# WireBender_Remix.net
KiCad netlist of a schematic drawn in EAGLE
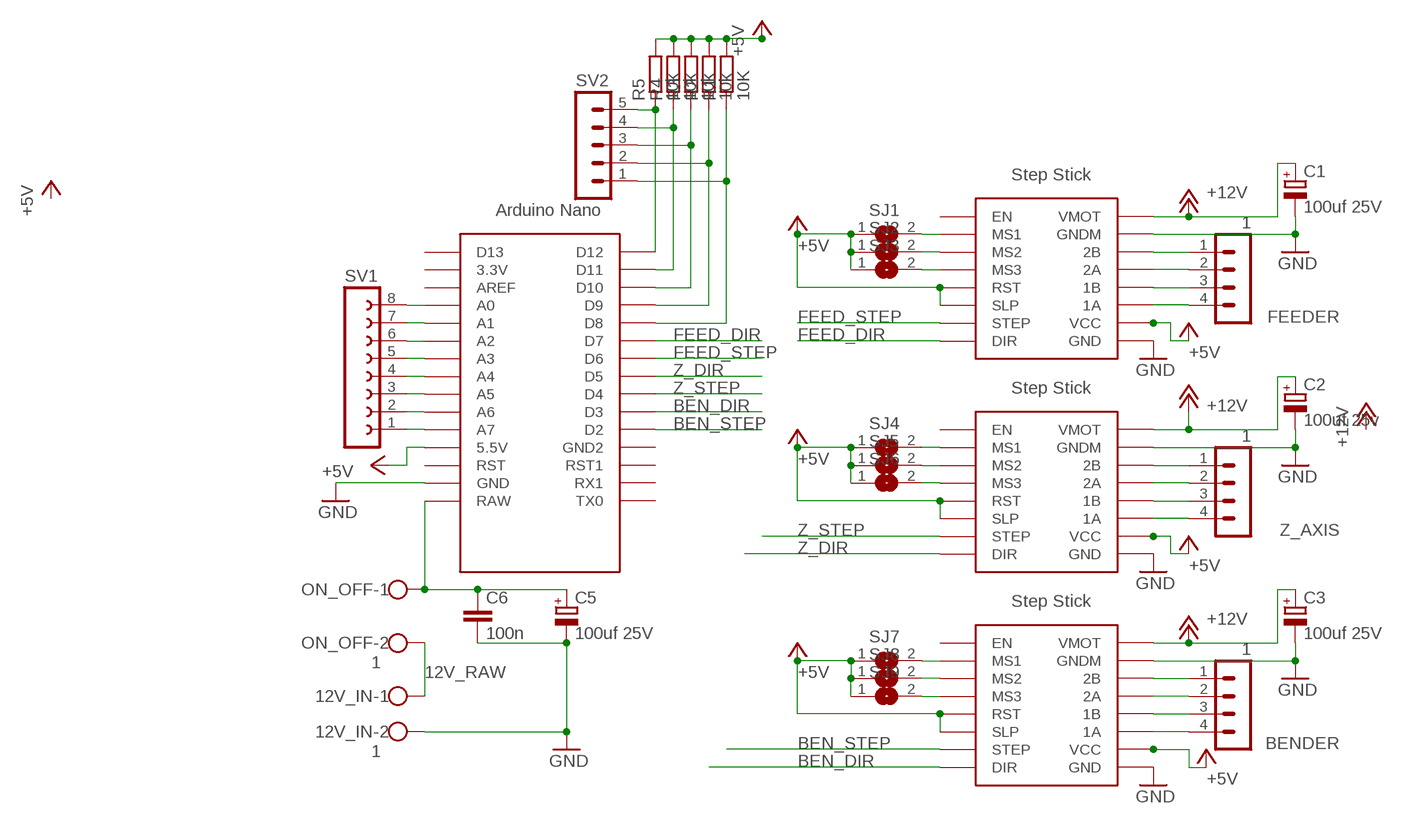
[diagram p0: schematic, sheet 1]

(export (version "E")
  (design (tool "Eeschema 10.0.6"))
  (components
    (comp (ref "12V_IN")
      (value "1")
      (footprint "eagle-import:W237-102")
      (fields (field (name "MPN") "237-102"))
      (libsource (lib "eagle-import") (part "W237-102"))
    )
    (comp (ref "BENDER")
      (value "1")
      (footprint "eagle-import:MA04-1")
      (libsource (lib "eagle-import") (part "MA04-1"))
    )
    (comp (ref "C1")
      (value "100uf 25V")
      (footprint "eagle-import:E3,5-8")
      (libsource (lib "eagle-import") (part "CPOL-EUE3.5-8"))
    )
    (comp (ref "C2")
      (value "100uf 25v")
      (footprint "eagle-import:E3,5-8")
      (libsource (lib "eagle-import") (part "CPOL-EUE3.5-8"))
    )
    (comp (ref "C3")
      (value "100uf 25V")
      (footprint "eagle-import:E3,5-8")
      (libsource (lib "eagle-import") (part "CPOL-EUE3.5-8"))
    )
    (comp (ref "C5")
      (value "100uf 25V")
      (footprint "eagle-import:E3,5-8")
      (libsource (lib "eagle-import") (part "CPOL-EUE3.5-8"))
    )
    (comp (ref "C6")
      (value "100n")
      (footprint "eagle-import:C025-030X050")
      (libsource (lib "eagle-import") (part "C-EU025-030X050"))
    )
    (comp (ref "FEEDER")
      (value "1")
      (footprint "eagle-import:MA04-1")
      (libsource (lib "eagle-import") (part "MA04-1"))
    )
    (comp (ref "FEED_DRV")
      (value "STEP-STICK")
      (footprint "eagle-import:STEP-STICK")
      (libsource (lib "eagle-import") (part "STEP-STICK"))
    )
    (comp (ref "ON_OFF")
      (value "1")
      (footprint "eagle-import:W237-102")
      (fields (field (name "MPN") "237-102"))
      (libsource (lib "eagle-import") (part "W237-102"))
    )
    (comp (ref "R1")
      (value "10K")
      (footprint "eagle-import:0207_7")
      (libsource (lib "eagle-import") (part "R-EU_0207/7"))
    )
    (comp (ref "R2")
      (value "10k")
      (footprint "eagle-import:0207_7")
      (libsource (lib "eagle-import") (part "R-EU_0207/7"))
    )
    (comp (ref "R3")
      (value "10k")
      (footprint "eagle-import:0207_7")
      (libsource (lib "eagle-import") (part "R-EU_0207/7"))
    )
    (comp (ref "R4")
      (value "10k")
      (footprint "eagle-import:0207_7")
      (libsource (lib "eagle-import") (part "R-EU_0207/7"))
    )
    (comp (ref "R5")
      (value "10k")
      (footprint "eagle-import:0207_7")
      (libsource (lib "eagle-import") (part "R-EU_0207/7"))
    )
    (comp (ref "SJ1")
      (value "SJW")
      (footprint "eagle-import:SJW")
      (libsource (lib "eagle-import") (part "SJW"))
    )
    (comp (ref "SJ2")
      (value "SJW")
      (footprint "eagle-import:SJW")
      (libsource (lib "eagle-import") (part "SJW"))
    )
    (comp (ref "SJ3")
      (value "SJW")
      (footprint "eagle-import:SJW")
      (libsource (lib "eagle-import") (part "SJW"))
    )
    (comp (ref "SJ4")
      (value "SJW")
      (footprint "eagle-import:SJW")
      (libsource (lib "eagle-import") (part "SJW"))
    )
    (comp (ref "SJ5")
      (value "SJW")
      (footprint "eagle-import:SJW")
      (libsource (lib "eagle-import") (part "SJW"))
    )
    (comp (ref "SJ6")
      (value "SJW")
      (footprint "eagle-import:SJW")
      (libsource (lib "eagle-import") (part "SJW"))
    )
    (comp (ref "SJ7")
      (value "SJW")
      (footprint "eagle-import:SJW")
      (libsource (lib "eagle-import") (part "SJW"))
    )
    (comp (ref "SJ8")
      (value "SJW")
      (footprint "eagle-import:SJW")
      (libsource (lib "eagle-import") (part "SJW"))
    )
    (comp (ref "SJ9")
      (value "SJW")
      (footprint "eagle-import:SJW")
      (libsource (lib "eagle-import") (part "SJW"))
    )
    (comp (ref "SV1")
      (value "FE08-1")
      (footprint "eagle-import:FE08")
      (libsource (lib "eagle-import") (part "FE08-1"))
    )
    (comp (ref "SV2")
      (value "MA05-1")
      (footprint "eagle-import:MA05-1")
      (libsource (lib "eagle-import") (part "MA05-1"))
    )
    (comp (ref "U$1")
      (value "NANO")
      (footprint "eagle-import:NANO")
      (libsource (lib "eagle-import") (part "NANO"))
    )
    (comp (ref "U$3")
      (value "STEP-STICK")
      (footprint "eagle-import:STEP-STICK")
      (libsource (lib "eagle-import") (part "STEP-STICK"))
    )
    (comp (ref "U$4")
      (value "STEP-STICK")
      (footprint "eagle-import:STEP-STICK")
      (libsource (lib "eagle-import") (part "STEP-STICK"))
    )
    (comp (ref "Z_AXIS")
      (value "1")
      (footprint "eagle-import:MA04-1")
      (libsource (lib "eagle-import") (part "MA04-1"))
    )
  )
  (nets
    (net (code "1") (name "+5V") (class "Default")
      (node (ref "FEED_DRV") (pin "RST") (pinfunction "RST_RST") (pintype "bidirectional"))
      (node (ref "FEED_DRV") (pin "SLP") (pinfunction "SLP_SLP") (pintype "bidirectional"))
      (node (ref "FEED_DRV") (pin "VCC") (pinfunction "VCC_VCC") (pintype "bidirectional"))
      (node (ref "R1") (pin "2") (pinfunction "2_2") (pintype "passive"))
      (node (ref "R2") (pin "2") (pinfunction "2_2") (pintype "passive"))
      (node (ref "R3") (pin "2") (pinfunction "2_2") (pintype "passive"))
      (node (ref "R4") (pin "2") (pinfunction "2_2") (pintype "passive"))
      (node (ref "R5") (pin "2") (pinfunction "2_2") (pintype "passive"))
      (node (ref "SJ1") (pin "1") (pinfunction "1_1") (pintype "passive"))
      (node (ref "SJ2") (pin "1") (pinfunction "1_1") (pintype "passive"))
      (node (ref "SJ3") (pin "1") (pinfunction "1_1") (pintype "passive"))
      (node (ref "SJ4") (pin "1") (pinfunction "1_1") (pintype "passive"))
      (node (ref "SJ5") (pin "1") (pinfunction "1_1") (pintype "passive"))
      (node (ref "SJ6") (pin "1") (pinfunction "1_1") (pintype "passive"))
      (node (ref "SJ7") (pin "1") (pinfunction "1_1") (pintype "passive"))
      (node (ref "SJ8") (pin "1") (pinfunction "1_1") (pintype "passive"))
      (node (ref "SJ9") (pin "1") (pinfunction "1_1") (pintype "passive"))
      (node (ref "U$1") (pin "5V") (pinfunction "5.5V_5V") (pintype "bidirectional"))
      (node (ref "U$3") (pin "RST") (pinfunction "RST_RST") (pintype "bidirectional"))
      (node (ref "U$3") (pin "SLP") (pinfunction "SLP_SLP") (pintype "bidirectional"))
      (node (ref "U$3") (pin "VCC") (pinfunction "VCC_VCC") (pintype "bidirectional"))
      (node (ref "U$4") (pin "RST") (pinfunction "RST_RST") (pintype "bidirectional"))
      (node (ref "U$4") (pin "SLP") (pinfunction "SLP_SLP") (pintype "bidirectional"))
      (node (ref "U$4") (pin "VCC") (pinfunction "VCC_VCC") (pintype "bidirectional"))
    )
    (net (code "2") (name "+12V") (class "Default")
      (node (ref "C1") (pin "+") (pinfunction "+_+") (pintype "passive"))
      (node (ref "C2") (pin "+") (pinfunction "+_+") (pintype "passive"))
      (node (ref "C3") (pin "+") (pinfunction "+_+") (pintype "passive"))
      (node (ref "FEED_DRV") (pin "VMOT") (pinfunction "VMOT_VMOT") (pintype "bidirectional"))
      (node (ref "U$3") (pin "VMOT") (pinfunction "VMOT_VMOT") (pintype "bidirectional"))
      (node (ref "U$4") (pin "VMOT") (pinfunction "VMOT_VMOT") (pintype "bidirectional"))
    )
    (net (code "3") (name "/12V_RAW") (class "Default")
      (node (ref "12V_IN") (pin "1") (pinfunction "KL_1") (pintype "passive"))
      (node (ref "ON_OFF") (pin "2") (pinfunction "KL_2") (pintype "passive"))
    )
    (net (code "4") (name "/BEN_DIR") (class "Default")
      (node (ref "U$1") (pin "D3") (pinfunction "D3_D3") (pintype "bidirectional"))
      (node (ref "U$4") (pin "DIR") (pinfunction "DIR_DIR") (pintype "bidirectional"))
    )
    (net (code "5") (name "/BEN_STEP") (class "Default")
      (node (ref "U$1") (pin "D2") (pinfunction "D2_D2") (pintype "bidirectional"))
      (node (ref "U$4") (pin "SPT") (pinfunction "STEP_SPT") (pintype "bidirectional"))
    )
    (net (code "6") (name "/FEED_DIR") (class "Default")
      (node (ref "FEED_DRV") (pin "DIR") (pinfunction "DIR_DIR") (pintype "bidirectional"))
      (node (ref "U$1") (pin "D7") (pinfunction "D7_D7") (pintype "bidirectional"))
    )
    (net (code "7") (name "/FEED_STEP") (class "Default")
      (node (ref "FEED_DRV") (pin "SPT") (pinfunction "STEP_SPT") (pintype "bidirectional"))
      (node (ref "U$1") (pin "D6") (pinfunction "D6_D6") (pintype "bidirectional"))
    )
    (net (code "8") (name "/Z_DIR") (class "Default")
      (node (ref "U$1") (pin "D5") (pinfunction "D5_D5") (pintype "bidirectional"))
      (node (ref "U$3") (pin "DIR") (pinfunction "DIR_DIR") (pintype "bidirectional"))
    )
    (net (code "9") (name "/Z_STEP") (class "Default")
      (node (ref "U$1") (pin "D4") (pinfunction "D4_D4") (pintype "bidirectional"))
      (node (ref "U$3") (pin "SPT") (pinfunction "STEP_SPT") (pintype "bidirectional"))
    )
    (net (code "10") (name "GND") (class "Default")
      (node (ref "12V_IN") (pin "2") (pinfunction "KL_2") (pintype "passive"))
      (node (ref "C1") (pin "-") (pinfunction "-_-") (pintype "passive"))
      (node (ref "C2") (pin "-") (pinfunction "-_-") (pintype "passive"))
      (node (ref "C3") (pin "-") (pinfunction "-_-") (pintype "passive"))
      (node (ref "C5") (pin "-") (pinfunction "-_-") (pintype "passive"))
      (node (ref "C6") (pin "2") (pinfunction "2_2") (pintype "passive"))
      (node (ref "FEED_DRV") (pin "GND") (pinfunction "GND_GND") (pintype "bidirectional"))
      (node (ref "FEED_DRV") (pin "GNDM") (pinfunction "GNDM_GNDM") (pintype "bidirectional"))
      (node (ref "U$1") (pin "GND") (pinfunction "GND_GND") (pintype "bidirectional"))
      (node (ref "U$3") (pin "GND") (pinfunction "GND_GND") (pintype "bidirectional"))
      (node (ref "U$3") (pin "GNDM") (pinfunction "GNDM_GNDM") (pintype "bidirectional"))
      (node (ref "U$4") (pin "GND") (pinfunction "GND_GND") (pintype "bidirectional"))
      (node (ref "U$4") (pin "GNDM") (pinfunction "GNDM_GNDM") (pintype "bidirectional"))
    )
    (net (code "11") (name "Net-(BENDER-Pad1)") (class "Default")
      (node (ref "BENDER") (pin "1") (pinfunction "1_1") (pintype "passive"))
      (node (ref "U$4") (pin "2B") (pinfunction "2B_2B") (pintype "bidirectional"))
    )
    (net (code "12") (name "Net-(BENDER-Pad2)") (class "Default")
      (node (ref "BENDER") (pin "2") (pinfunction "2_2") (pintype "passive"))
      (node (ref "U$4") (pin "2A") (pinfunction "2A_2A") (pintype "bidirectional"))
    )
    (net (code "13") (name "Net-(BENDER-Pad3)") (class "Default")
      (node (ref "BENDER") (pin "3") (pinfunction "3_3") (pintype "passive"))
      (node (ref "U$4") (pin "1B") (pinfunction "1B_1B") (pintype "bidirectional"))
    )
    (net (code "14") (name "Net-(BENDER-Pad4)") (class "Default")
      (node (ref "BENDER") (pin "4") (pinfunction "4_4") (pintype "passive"))
      (node (ref "U$4") (pin "1A") (pinfunction "1A_1A") (pintype "bidirectional"))
    )
    (net (code "15") (name "Net-(FEEDER-Pad1)") (class "Default")
      (node (ref "FEEDER") (pin "1") (pinfunction "1_1") (pintype "passive"))
      (node (ref "FEED_DRV") (pin "2B") (pinfunction "2B_2B") (pintype "bidirectional"))
    )
    (net (code "16") (name "Net-(FEEDER-Pad2)") (class "Default")
      (node (ref "FEEDER") (pin "2") (pinfunction "2_2") (pintype "passive"))
      (node (ref "FEED_DRV") (pin "2A") (pinfunction "2A_2A") (pintype "bidirectional"))
    )
    (net (code "17") (name "Net-(FEEDER-Pad3)") (class "Default")
      (node (ref "FEEDER") (pin "3") (pinfunction "3_3") (pintype "passive"))
      (node (ref "FEED_DRV") (pin "1B") (pinfunction "1B_1B") (pintype "bidirectional"))
    )
    (net (code "18") (name "Net-(FEEDER-Pad4)") (class "Default")
      (node (ref "FEEDER") (pin "4") (pinfunction "4_4") (pintype "passive"))
      (node (ref "FEED_DRV") (pin "1A") (pinfunction "1A_1A") (pintype "bidirectional"))
    )
    (net (code "19") (name "Net-(FEED_DRV-PadMS1)") (class "Default")
      (node (ref "FEED_DRV") (pin "MS1") (pinfunction "MS1_MS1") (pintype "bidirectional"))
      (node (ref "SJ1") (pin "2") (pinfunction "2_2") (pintype "passive"))
    )
    (net (code "20") (name "Net-(FEED_DRV-PadMS2)") (class "Default")
      (node (ref "FEED_DRV") (pin "MS2") (pinfunction "MS2_MS2") (pintype "bidirectional"))
      (node (ref "SJ2") (pin "2") (pinfunction "2_2") (pintype "passive"))
    )
    (net (code "21") (name "Net-(FEED_DRV-PadMS3)") (class "Default")
      (node (ref "FEED_DRV") (pin "MS3") (pinfunction "MS3_MS3") (pintype "bidirectional"))
      (node (ref "SJ3") (pin "2") (pinfunction "2_2") (pintype "passive"))
    )
    (net (code "22") (name "Net-(ON_OFFA-KL)") (class "Default")
      (node (ref "C5") (pin "+") (pinfunction "+_+") (pintype "passive"))
      (node (ref "C6") (pin "1") (pinfunction "1_1") (pintype "passive"))
      (node (ref "ON_OFF") (pin "1") (pinfunction "KL_1") (pintype "passive"))
      (node (ref "U$1") (pin "RAW") (pinfunction "RAW_RAW") (pintype "bidirectional"))
    )
    (net (code "23") (name "Net-(R1-Pad1)") (class "Default")
      (node (ref "R1") (pin "1") (pinfunction "1_1") (pintype "passive"))
      (node (ref "SV2") (pin "1") (pinfunction "1_1") (pintype "passive"))
      (node (ref "U$1") (pin "D8") (pinfunction "D8_D8") (pintype "bidirectional"))
    )
    (net (code "24") (name "Net-(R2-Pad1)") (class "Default")
      (node (ref "R2") (pin "1") (pinfunction "1_1") (pintype "passive"))
      (node (ref "SV2") (pin "2") (pinfunction "2_2") (pintype "passive"))
      (node (ref "U$1") (pin "D9") (pinfunction "D9_D9") (pintype "bidirectional"))
    )
    (net (code "25") (name "Net-(R3-Pad1)") (class "Default")
      (node (ref "R3") (pin "1") (pinfunction "1_1") (pintype "passive"))
      (node (ref "SV2") (pin "3") (pinfunction "3_3") (pintype "passive"))
      (node (ref "U$1") (pin "D10") (pinfunction "D10_D10") (pintype "bidirectional"))
    )
    (net (code "26") (name "Net-(R4-Pad1)") (class "Default")
      (node (ref "R4") (pin "1") (pinfunction "1_1") (pintype "passive"))
      (node (ref "SV2") (pin "4") (pinfunction "4_4") (pintype "passive"))
      (node (ref "U$1") (pin "D11") (pinfunction "D11_D11") (pintype "bidirectional"))
    )
    (net (code "27") (name "Net-(R5-Pad1)") (class "Default")
      (node (ref "R5") (pin "1") (pinfunction "1_1") (pintype "passive"))
      (node (ref "SV2") (pin "5") (pinfunction "5_5") (pintype "passive"))
      (node (ref "U$1") (pin "D12") (pinfunction "D12_D12") (pintype "bidirectional"))
    )
    (net (code "28") (name "Net-(SJ4-Pad2)") (class "Default")
      (node (ref "SJ4") (pin "2") (pinfunction "2_2") (pintype "passive"))
      (node (ref "U$3") (pin "MS1") (pinfunction "MS1_MS1") (pintype "bidirectional"))
    )
    (net (code "29") (name "Net-(SJ5-Pad2)") (class "Default")
      (node (ref "SJ5") (pin "2") (pinfunction "2_2") (pintype "passive"))
      (node (ref "U$3") (pin "MS2") (pinfunction "MS2_MS2") (pintype "bidirectional"))
    )
    (net (code "30") (name "Net-(SJ6-Pad2)") (class "Default")
      (node (ref "SJ6") (pin "2") (pinfunction "2_2") (pintype "passive"))
      (node (ref "U$3") (pin "MS3") (pinfunction "MS3_MS3") (pintype "bidirectional"))
    )
    (net (code "31") (name "Net-(SJ7-Pad2)") (class "Default")
      (node (ref "SJ7") (pin "2") (pinfunction "2_2") (pintype "passive"))
      (node (ref "U$4") (pin "MS1") (pinfunction "MS1_MS1") (pintype "bidirectional"))
    )
    (net (code "32") (name "Net-(SJ8-Pad2)") (class "Default")
      (node (ref "SJ8") (pin "2") (pinfunction "2_2") (pintype "passive"))
      (node (ref "U$4") (pin "MS2") (pinfunction "MS2_MS2") (pintype "bidirectional"))
    )
    (net (code "33") (name "Net-(SJ9-Pad2)") (class "Default")
      (node (ref "SJ9") (pin "2") (pinfunction "2_2") (pintype "passive"))
      (node (ref "U$4") (pin "MS3") (pinfunction "MS3_MS3") (pintype "bidirectional"))
    )
    (net (code "34") (name "Net-(SV1-Pad1)") (class "Default")
      (node (ref "SV1") (pin "1") (pinfunction "1_1") (pintype "passive"))
      (node (ref "U$1") (pin "A7") (pinfunction "A7_A7") (pintype "bidirectional"))
    )
    (net (code "35") (name "Net-(SV1-Pad2)") (class "Default")
      (node (ref "SV1") (pin "2") (pinfunction "2_2") (pintype "passive"))
      (node (ref "U$1") (pin "A6") (pinfunction "A6_A6") (pintype "bidirectional"))
    )
    (net (code "36") (name "Net-(SV1-Pad3)") (class "Default")
      (node (ref "SV1") (pin "3") (pinfunction "3_3") (pintype "passive"))
      (node (ref "U$1") (pin "A5") (pinfunction "A5_A5") (pintype "bidirectional"))
    )
    (net (code "37") (name "Net-(SV1-Pad4)") (class "Default")
      (node (ref "SV1") (pin "4") (pinfunction "4_4") (pintype "passive"))
      (node (ref "U$1") (pin "A4") (pinfunction "A4_A4") (pintype "bidirectional"))
    )
    (net (code "38") (name "Net-(SV1-Pad5)") (class "Default")
      (node (ref "SV1") (pin "5") (pinfunction "5_5") (pintype "passive"))
      (node (ref "U$1") (pin "A3") (pinfunction "A3_A3") (pintype "bidirectional"))
    )
    (net (code "39") (name "Net-(SV1-Pad6)") (class "Default")
      (node (ref "SV1") (pin "6") (pinfunction "6_6") (pintype "passive"))
      (node (ref "U$1") (pin "A2") (pinfunction "A2_A2") (pintype "bidirectional"))
    )
    (net (code "40") (name "Net-(SV1-Pad7)") (class "Default")
      (node (ref "SV1") (pin "7") (pinfunction "7_7") (pintype "passive"))
      (node (ref "U$1") (pin "A1") (pinfunction "A1_A1") (pintype "bidirectional"))
    )
    (net (code "41") (name "Net-(SV1-Pad8)") (class "Default")
      (node (ref "SV1") (pin "8") (pinfunction "8_8") (pintype "passive"))
      (node (ref "U$1") (pin "A0") (pinfunction "A0_A0") (pintype "bidirectional"))
    )
    (net (code "42") (name "Net-(U$3-Pad1A)") (class "Default")
      (node (ref "U$3") (pin "1A") (pinfunction "1A_1A") (pintype "bidirectional"))
      (node (ref "Z_AXIS") (pin "4") (pinfunction "4_4") (pintype "passive"))
    )
    (net (code "43") (name "Net-(U$3-Pad1B)") (class "Default")
      (node (ref "U$3") (pin "1B") (pinfunction "1B_1B") (pintype "bidirectional"))
      (node (ref "Z_AXIS") (pin "3") (pinfunction "3_3") (pintype "passive"))
    )
    (net (code "44") (name "Net-(U$3-Pad2A)") (class "Default")
      (node (ref "U$3") (pin "2A") (pinfunction "2A_2A") (pintype "bidirectional"))
      (node (ref "Z_AXIS") (pin "2") (pinfunction "2_2") (pintype "passive"))
    )
    (net (code "45") (name "Net-(U$3-Pad2B)") (class "Default")
      (node (ref "U$3") (pin "2B") (pinfunction "2B_2B") (pintype "bidirectional"))
      (node (ref "Z_AXIS") (pin "1") (pinfunction "1_1") (pintype "passive"))
    )
    (net (code "46") (name "unconnected-(FEED_DRV-PadEN)") (class "Default")
      (node (ref "FEED_DRV") (pin "EN") (pinfunction "EN_EN") (pintype "bidirectional"))
    )
    (net (code "47") (name "unconnected-(U$1-GND2-PadGND1)") (class "Default")
      (node (ref "U$1") (pin "GND1") (pinfunction "GND2_GND1") (pintype "bidirectional"))
    )
    (net (code "48") (name "unconnected-(U$1-Pad3.3V)") (class "Default")
      (node (ref "U$1") (pin "3.3V") (pinfunction "3.3V_3.3V") (pintype "bidirectional"))
    )
    (net (code "49") (name "unconnected-(U$1-PadAREF)") (class "Default")
      (node (ref "U$1") (pin "AREF") (pinfunction "AREF_AREF") (pintype "bidirectional"))
    )
    (net (code "50") (name "unconnected-(U$1-PadD13)") (class "Default")
      (node (ref "U$1") (pin "D13") (pinfunction "D13_D13") (pintype "bidirectional"))
    )
    (net (code "51") (name "unconnected-(U$1-PadRST)") (class "Default")
      (node (ref "U$1") (pin "RST") (pinfunction "RST_RST") (pintype "bidirectional"))
    )
    (net (code "52") (name "unconnected-(U$1-PadRST1)") (class "Default")
      (node (ref "U$1") (pin "RST1") (pinfunction "RST1_RST1") (pintype "bidirectional"))
    )
    (net (code "53") (name "unconnected-(U$1-PadRX1)") (class "Default")
      (node (ref "U$1") (pin "RX1") (pinfunction "RX1_RX1") (pintype "bidirectional"))
    )
    (net (code "54") (name "unconnected-(U$1-PadTX0)") (class "Default")
      (node (ref "U$1") (pin "TX0") (pinfunction "TX0_TX0") (pintype "bidirectional"))
    )
    (net (code "55") (name "unconnected-(U$3-PadEN)") (class "Default")
      (node (ref "U$3") (pin "EN") (pinfunction "EN_EN") (pintype "bidirectional"))
    )
    (net (code "56") (name "unconnected-(U$4-PadEN)") (class "Default")
      (node (ref "U$4") (pin "EN") (pinfunction "EN_EN") (pintype "bidirectional"))
    )
  )
)
